# design.net
KiCad netlist of a schematic drawn in EasyEDA Pro
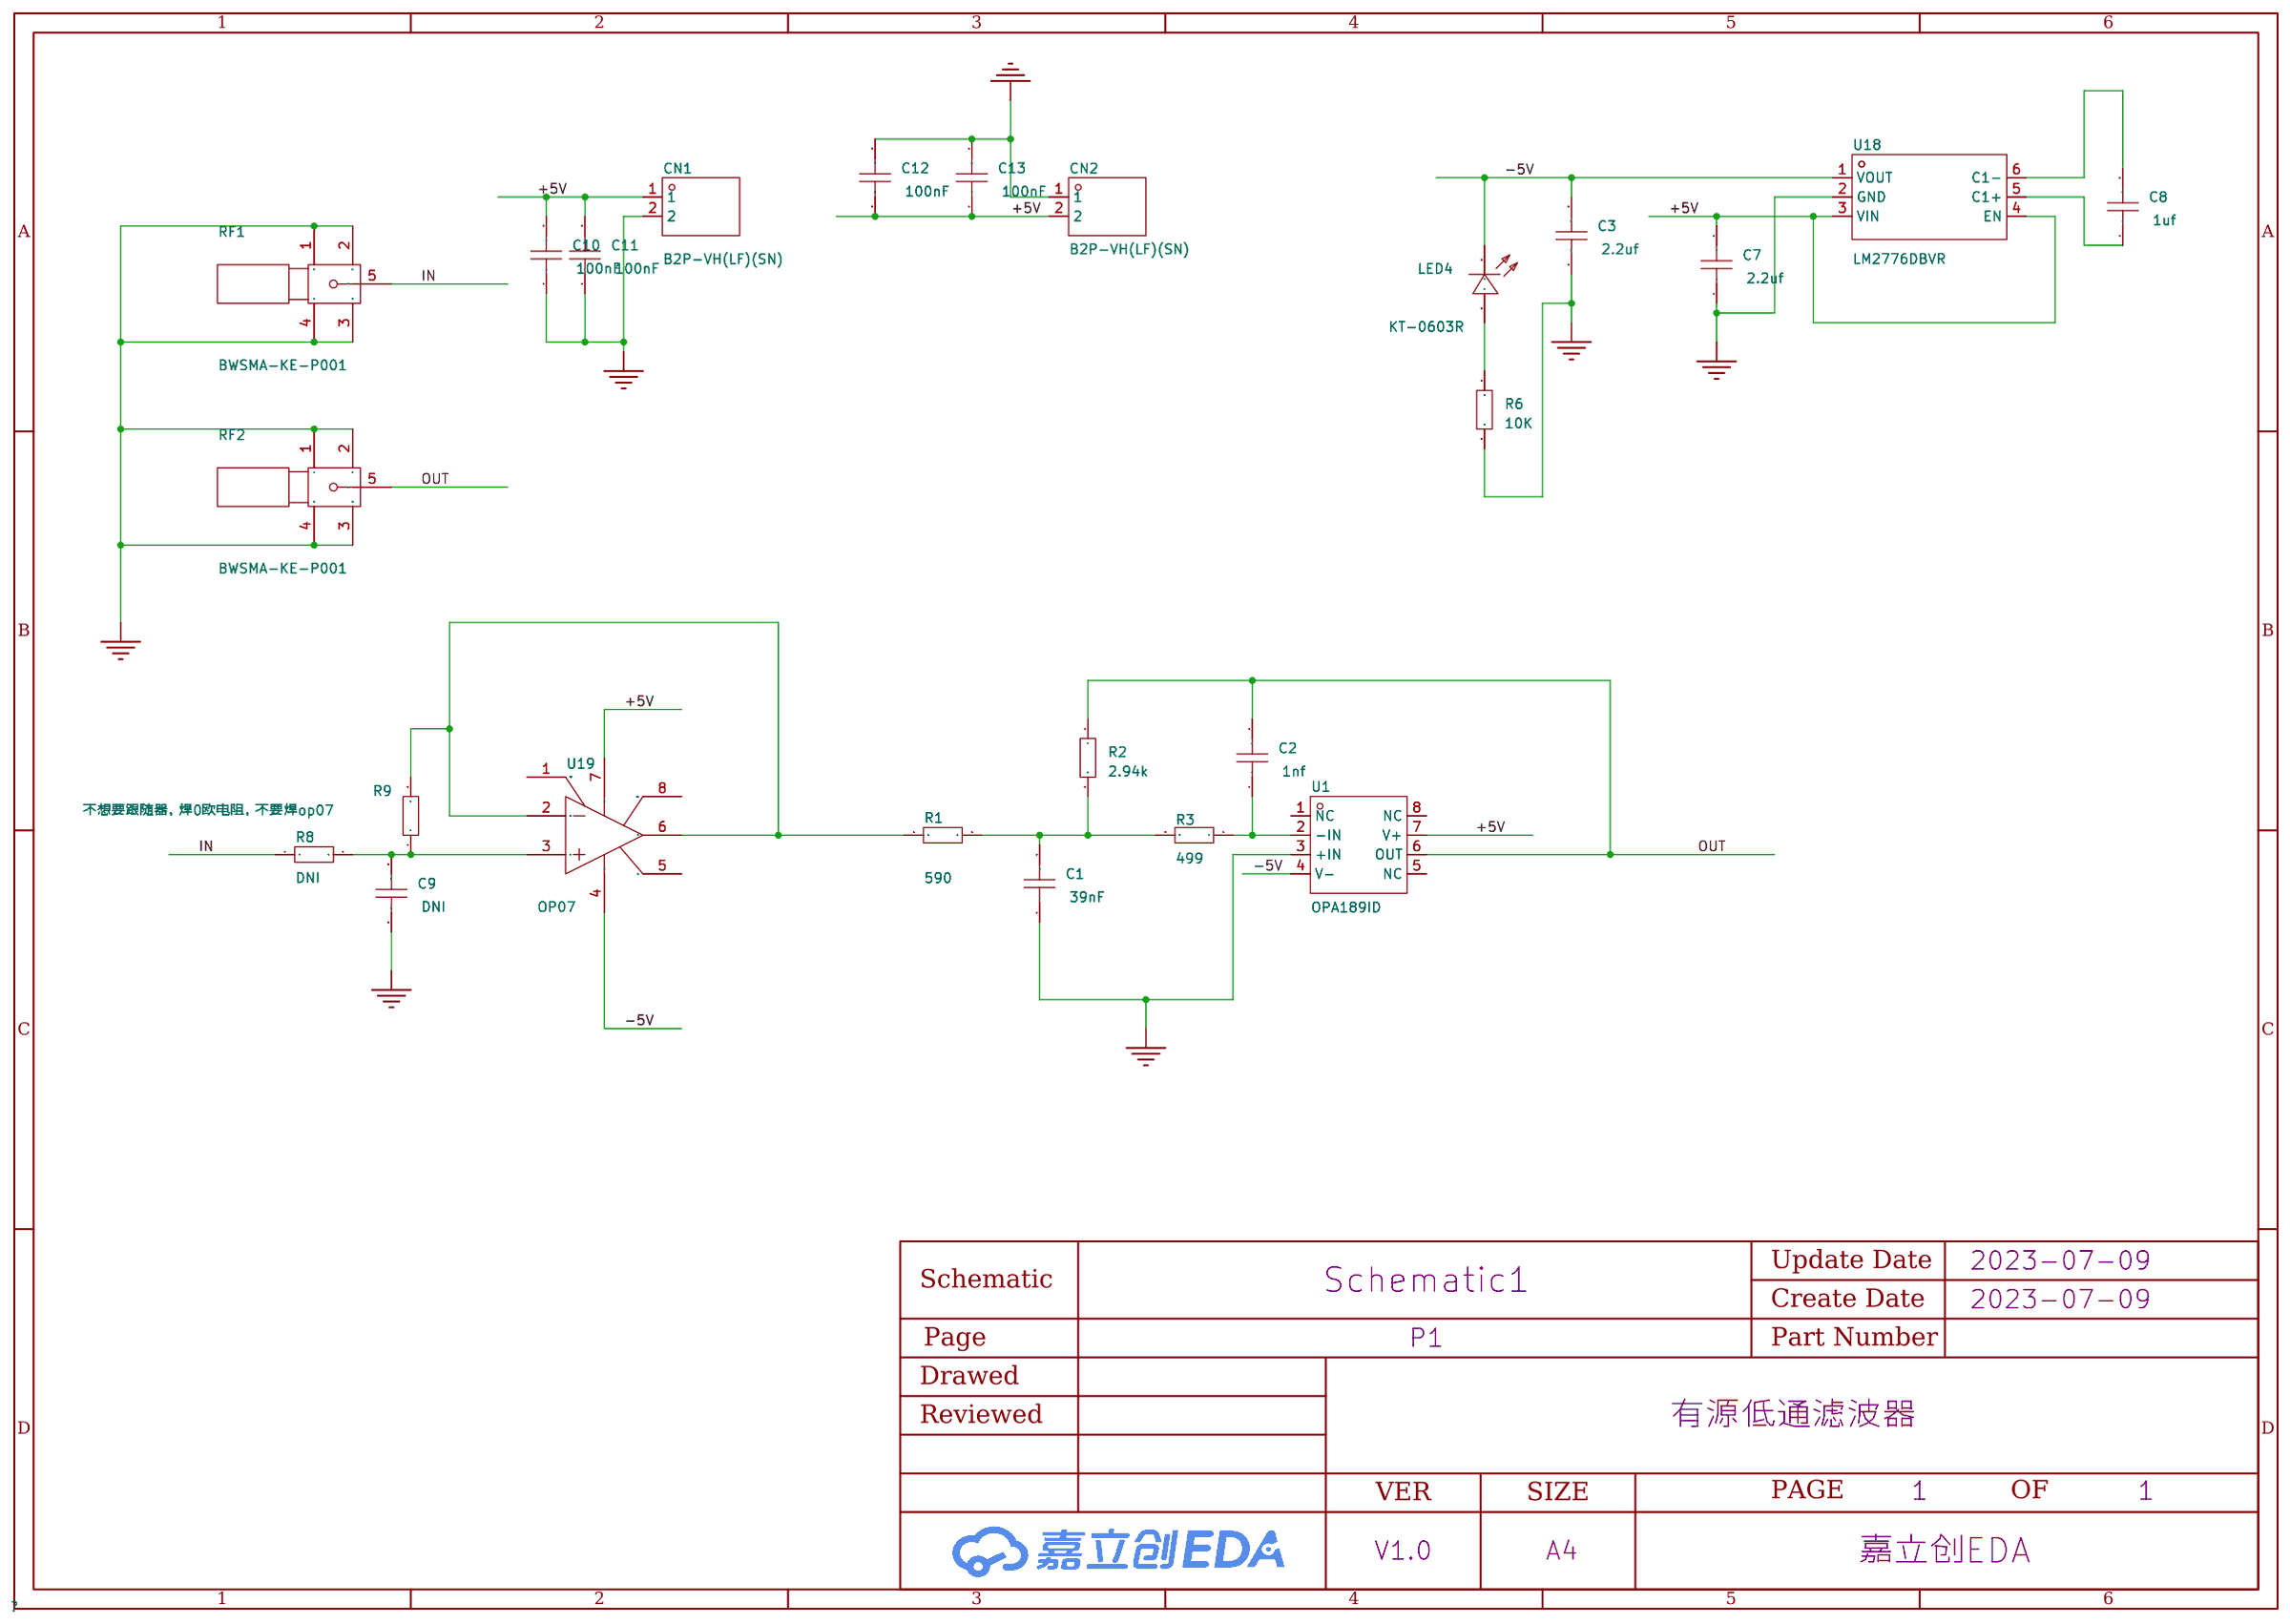
[diagram p0: schematic sheet]

(export (version "E")
  (design (tool "Eeschema 10.0.6"))
  (components
    (comp (ref "C1")
      (value "39nF")
      (footprint "easyedapro:C0603")
      (libsource (lib "easyedapro") (part "CapAcitance"))
    )
    (comp (ref "C2")
      (value "1nf")
      (footprint "easyedapro:C0603")
      (libsource (lib "easyedapro") (part "CapAcitance"))
    )
    (comp (ref "C3")
      (value "2.2uf")
      (footprint "easyedapro:C0603")
      (libsource (lib "easyedapro") (part "CapAcitance"))
    )
    (comp (ref "C7")
      (value "2.2uf")
      (footprint "easyedapro:C0603")
      (libsource (lib "easyedapro") (part "CapAcitance"))
    )
    (comp (ref "C8")
      (value "1uf")
      (footprint "easyedapro:C0603")
      (libsource (lib "easyedapro") (part "CapAcitance"))
    )
    (comp (ref "C9")
      (value "DNI")
      (footprint "easyedapro:C0603")
      (libsource (lib "easyedapro") (part "CapAcitance"))
    )
    (comp (ref "C10")
      (value "100nF")
      (footprint "easyedapro:C0603")
      (libsource (lib "easyedapro") (part "CapAcitance"))
    )
    (comp (ref "C11")
      (value "100nF")
      (footprint "easyedapro:C0603")
      (libsource (lib "easyedapro") (part "CapAcitance"))
    )
    (comp (ref "C12")
      (value "100nF")
      (footprint "easyedapro:C0603")
      (libsource (lib "easyedapro") (part "CapAcitance"))
    )
    (comp (ref "C13")
      (value "100nF")
      (footprint "easyedapro:C0603")
      (libsource (lib "easyedapro") (part "CapAcitance"))
    )
    (comp (ref "CN1")
      (value "B2P-VH(LF)(SN)")
      (footprint "easyedapro:CONN-TH_B2P-VH-LF-SN")
      (description "参考系列:VH;间距:3.96mm;插针结构:1x2P;排数:1;每排PIN数:2;行距:-;安装方式:-;触头材质:黄铜;")
      (fields (field (name "Manufacturer") "JST"))
      (libsource (lib "easyedapro") (part "B2P-VH (LF)(SN)"))
    )
    (comp (ref "CN2")
      (value "B2P-VH(LF)(SN)")
      (footprint "easyedapro:CONN-TH_B2P-VH-LF-SN")
      (description "参考系列:VH;间距:3.96mm;插针结构:1x2P;排数:1;每排PIN数:2;行距:-;安装方式:-;触头材质:黄铜;")
      (fields (field (name "Manufacturer") "JST"))
      (libsource (lib "easyedapro") (part "B2P-VH (LF)(SN)"))
    )
    (comp (ref "LED4")
      (value "KT-0603R")
      (footprint "easyedapro:LED0603-RD")
      (description "发光颜色:红灯;二极管配置:-;透镜颜色:-;主波长:-;色温:-;功率:-;发光角度:-;安装方式:-;工作温度:-40℃~+85℃;")
      (fields (field (name "Manufacturer") "KENTO"))
      (libsource (lib "easyedapro") (part "KT-0603R"))
    )
    (comp (ref "R1") (value "590") (footprint "easyedapro:R0603") (libsource (lib "easyedapro") (part "电阻")))
    (comp (ref "R2")
      (value "2.94k")
      (footprint "easyedapro:R0603")
      (libsource (lib "easyedapro") (part "电阻"))
    )
    (comp (ref "R3") (value "499") (footprint "easyedapro:R0603") (libsource (lib "easyedapro") (part "电阻")))
    (comp (ref "R6") (value "10K") (footprint "easyedapro:R0603") (libsource (lib "easyedapro") (part "电阻")))
    (comp (ref "R8") (value "DNI") (footprint "easyedapro:R0603") (libsource (lib "easyedapro") (part "电阻")))
    (comp (ref "R9")
      (value "不想要跟随器，焊0欧电阻，不要焊op07")
      (footprint "easyedapro:R0603")
      (libsource (lib "easyedapro") (part "电阻"))
    )
    (comp (ref "RF1")
      (value "BWSMA-KE-P001")
      (footprint "easyedapro:SMA-SMD_BWSMA-KE-P001")
      (description "连接器类型:板端;射频系列:SMA;接口类型:内孔;端口数量:1;阻抗:50Ω;频率-最大值:12.4GHz;样式:偏脚;接口直径:5.2mm;接口长度/高度:-;工作温度范围:-;")
      (fields (field (name "Manufacturer") "BAT WIRELESS(蝙蝠无线)"))
      (libsource (lib "easyedapro") (part "BWSMA-KE-P001"))
    )
    (comp (ref "RF2")
      (value "BWSMA-KE-P001")
      (footprint "easyedapro:SMA-SMD_BWSMA-KE-P001")
      (description "连接器类型:板端;射频系列:SMA;接口类型:内孔;端口数量:1;阻抗:50Ω;频率-最大值:12.4GHz;样式:偏脚;接口直径:5.2mm;接口长度/高度:-;工作温度范围:-;")
      (fields (field (name "Manufacturer") "BAT WIRELESS(蝙蝠无线)"))
      (libsource (lib "easyedapro") (part "BWSMA-KE-P001"))
    )
    (comp (ref "U1")
      (value "OPA189ID")
      (footprint "easyedapro:SOIC-8_L4.9-W3.9-P1.27-LS6.0-BL")
      (description "单路、14MHz、多路复用器友好型、低噪声、零漂移 、RRO、CMOS 精密运算放大器 8-SOIC -40 to 125")
      (fields (field (name "Manufacturer") "TI(德州仪器)"))
      (libsource (lib "easyedapro") (part "OPA189ID"))
    )
    (comp (ref "U18")
      (value "LM2776DBVR")
      (footprint "easyedapro:SOT-23-6_L2.9-W1.6-P0.95-LS2.8-BR")
      (description "可输出电流:200mA;开关工作频率:2MHz;输出类型:Fixed;输出电压的路数:1;功能类型:Ratiometric;输出配置:Negative;")
      (fields (field (name "Manufacturer") "TI(德州仪器)"))
      (libsource (lib "easyedapro") (part "LM2776DBVR"))
    )
    (comp (ref "U19")
      (value "OP07")
      (footprint "easyedapro:SOP-8_L4.9-W3.9-P1.27-LS6.0-BL")
      (description "放大器组数:-;")
      (fields (field (name "Manufacturer") "杭州瑞盟"))
      (libsource (lib "easyedapro") (part "OP07"))
    )
  )
  (nets
    (net (code "1") (name "/+5V") (class "Default")
      (node (ref "C10") (pin "2") (pinfunction "2_2") (pintype "input"))
      (node (ref "C11") (pin "2") (pinfunction "2_2") (pintype "input"))
      (node (ref "C12") (pin "1") (pinfunction "1_1") (pintype "input"))
      (node (ref "C13") (pin "1") (pinfunction "1_1") (pintype "input"))
      (node (ref "C7") (pin "2") (pinfunction "2_2") (pintype "input"))
      (node (ref "CN1") (pin "1") (pinfunction "1_1") (pintype "input"))
      (node (ref "CN2") (pin "2") (pinfunction "2_2") (pintype "input"))
      (node (ref "U1") (pin "7") (pinfunction "V+_7") (pintype "input"))
      (node (ref "U18") (pin "3") (pinfunction "VIN_3") (pintype "input"))
      (node (ref "U18") (pin "4") (pinfunction "EN_4") (pintype "input"))
      (node (ref "U19") (pin "7") (pinfunction "V+_7") (pintype "input"))
    )
    (net (code "2") (name "/-5V") (class "Default")
      (node (ref "C3") (pin "2") (pinfunction "2_2") (pintype "input"))
      (node (ref "LED4") (pin "1") (pinfunction "K_1") (pintype "input"))
      (node (ref "U1") (pin "4") (pinfunction "V-_4") (pintype "input"))
      (node (ref "U18") (pin "1") (pinfunction "VOUT_1") (pintype "input"))
      (node (ref "U19") (pin "4") (pinfunction "V-_4") (pintype "input"))
    )
    (net (code "3") (name "/IN") (class "Default")
      (node (ref "R8") (pin "1") (pinfunction "1_1") (pintype "input"))
      (node (ref "RF1") (pin "5") (pinfunction "5_5") (pintype "input"))
    )
    (net (code "4") (name "/OUT") (class "Default")
      (node (ref "C2") (pin "2") (pinfunction "2_2") (pintype "input"))
      (node (ref "R2") (pin "1") (pinfunction "1_1") (pintype "input"))
      (node (ref "RF2") (pin "5") (pinfunction "5_5") (pintype "input"))
      (node (ref "U1") (pin "6") (pinfunction "OUT_6") (pintype "input"))
    )
    (net (code "5") (name "GND") (class "Default")
      (node (ref "C1") (pin "1") (pinfunction "1_1") (pintype "input"))
      (node (ref "C10") (pin "1") (pinfunction "1_1") (pintype "input"))
      (node (ref "C11") (pin "1") (pinfunction "1_1") (pintype "input"))
      (node (ref "C12") (pin "2") (pinfunction "2_2") (pintype "input"))
      (node (ref "C13") (pin "2") (pinfunction "2_2") (pintype "input"))
      (node (ref "C3") (pin "1") (pinfunction "1_1") (pintype "input"))
      (node (ref "C7") (pin "1") (pinfunction "1_1") (pintype "input"))
      (node (ref "C9") (pin "1") (pinfunction "1_1") (pintype "input"))
      (node (ref "CN1") (pin "2") (pinfunction "2_2") (pintype "input"))
      (node (ref "CN2") (pin "1") (pinfunction "1_1") (pintype "input"))
      (node (ref "R6") (pin "2") (pinfunction "2_2") (pintype "input"))
      (node (ref "RF1") (pin "1") (pinfunction "1_1") (pintype "input"))
      (node (ref "RF1") (pin "2") (pinfunction "2_2") (pintype "input"))
      (node (ref "RF1") (pin "3") (pinfunction "3_3") (pintype "input"))
      (node (ref "RF1") (pin "4") (pinfunction "4_4") (pintype "input"))
      (node (ref "RF2") (pin "1") (pinfunction "1_1") (pintype "input"))
      (node (ref "RF2") (pin "2") (pinfunction "2_2") (pintype "input"))
      (node (ref "RF2") (pin "3") (pinfunction "3_3") (pintype "input"))
      (node (ref "RF2") (pin "4") (pinfunction "4_4") (pintype "input"))
      (node (ref "U1") (pin "3") (pinfunction "+IN_3") (pintype "input"))
      (node (ref "U18") (pin "2") (pinfunction "GND_2") (pintype "input"))
    )
    (net (code "6") (name "Net-(C1-Pad2)") (class "Default")
      (node (ref "C1") (pin "2") (pinfunction "2_2") (pintype "input"))
      (node (ref "R1") (pin "2") (pinfunction "2_2") (pintype "input"))
      (node (ref "R2") (pin "2") (pinfunction "2_2") (pintype "input"))
      (node (ref "R3") (pin "2") (pinfunction "2_2") (pintype "input"))
    )
    (net (code "7") (name "Net-(LED4-A)") (class "Default")
      (node (ref "LED4") (pin "2") (pinfunction "A_2") (pintype "input"))
      (node (ref "R6") (pin "1") (pinfunction "1_1") (pintype "input"))
    )
    (net (code "8") (name "Net-(U1--IN)") (class "Default")
      (node (ref "C2") (pin "1") (pinfunction "1_1") (pintype "input"))
      (node (ref "R3") (pin "1") (pinfunction "1_1") (pintype "input"))
      (node (ref "U1") (pin "2") (pinfunction "-IN_2") (pintype "input"))
    )
    (net (code "9") (name "Net-(U18-C1+)") (class "Default")
      (node (ref "C8") (pin "1") (pinfunction "1_1") (pintype "input"))
      (node (ref "U18") (pin "5") (pinfunction "C1+_5") (pintype "input"))
    )
    (net (code "10") (name "Net-(U18-C1-)") (class "Default")
      (node (ref "C8") (pin "2") (pinfunction "2_2") (pintype "input"))
      (node (ref "U18") (pin "6") (pinfunction "C1-_6") (pintype "input"))
    )
    (net (code "11") (name "Net-(U19-IN+)") (class "Default")
      (node (ref "C9") (pin "2") (pinfunction "2_2") (pintype "input"))
      (node (ref "R8") (pin "2") (pinfunction "2_2") (pintype "input"))
      (node (ref "R9") (pin "1") (pinfunction "1_1") (pintype "input"))
      (node (ref "U19") (pin "3") (pinfunction "IN+_3") (pintype "input"))
    )
    (net (code "12") (name "Net-(U19-IN-)") (class "Default")
      (node (ref "R1") (pin "1") (pinfunction "1_1") (pintype "input"))
      (node (ref "R9") (pin "2") (pinfunction "2_2") (pintype "input"))
      (node (ref "U19") (pin "2") (pinfunction "IN-_2") (pintype "input"))
      (node (ref "U19") (pin "6") (pinfunction "OUT_6") (pintype "output"))
    )
    (net (code "13") (name "unconnected-(U1-NC-Pad1)") (class "Default")
      (node (ref "U1") (pin "1") (pinfunction "NC_1") (pintype "input"))
    )
    (net (code "14") (name "unconnected-(U1-NC-Pad5)") (class "Default")
      (node (ref "U1") (pin "5") (pinfunction "NC_5") (pintype "input"))
    )
    (net (code "15") (name "unconnected-(U1-NC-Pad8)") (class "Default")
      (node (ref "U1") (pin "8") (pinfunction "NC_8") (pintype "input"))
    )
    (net (code "16") (name "unconnected-(U19-NC-Pad5)") (class "Default")
      (node (ref "U19") (pin "5") (pinfunction "NC_5") (pintype "input"))
    )
    (net (code "17") (name "unconnected-(U19-VOS_TRIM-Pad1)") (class "Default")
      (node (ref "U19") (pin "1") (pinfunction "VOS_TRIM_1") (pintype "input"))
    )
    (net (code "18") (name "unconnected-(U19-VOS_TRIM-Pad8)") (class "Default")
      (node (ref "U19") (pin "8") (pinfunction "VOS_TRIM_8") (pintype "input"))
    )
  )
)
